# benjolin_1_0.net
KiCad netlist of a schematic drawn in EAGLE
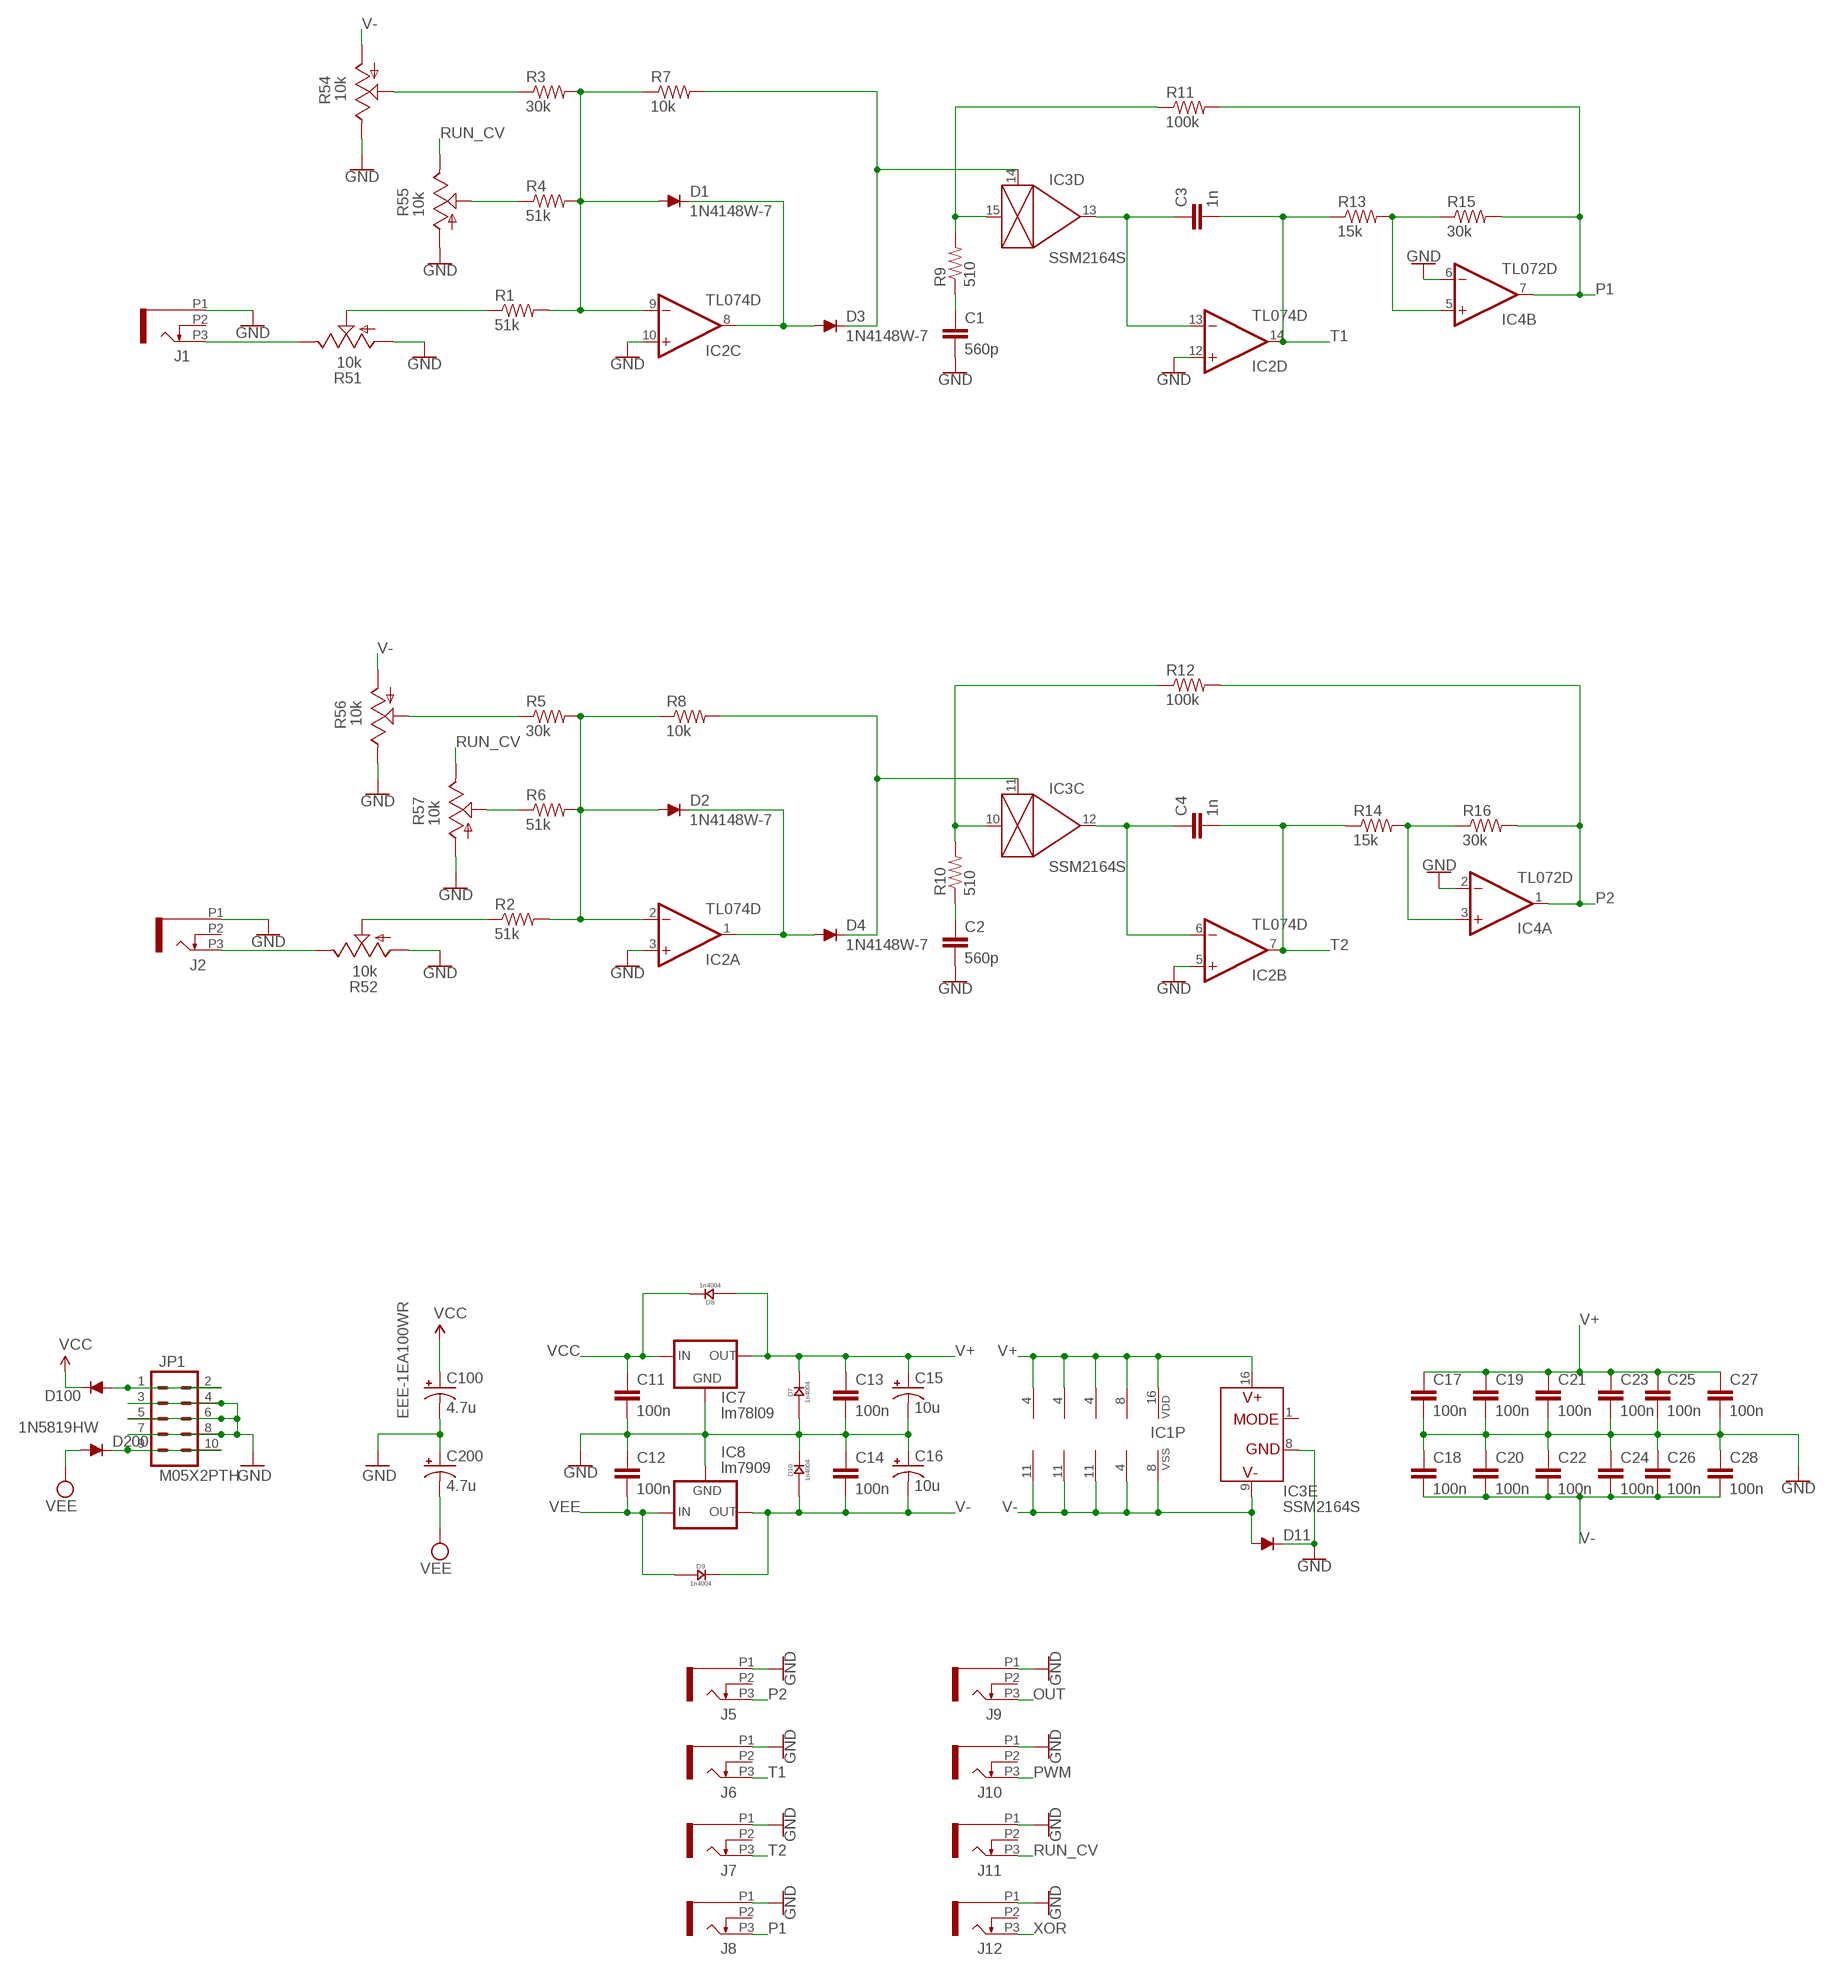
[diagram p0: schematic, sheet 1, part 1 of 2]
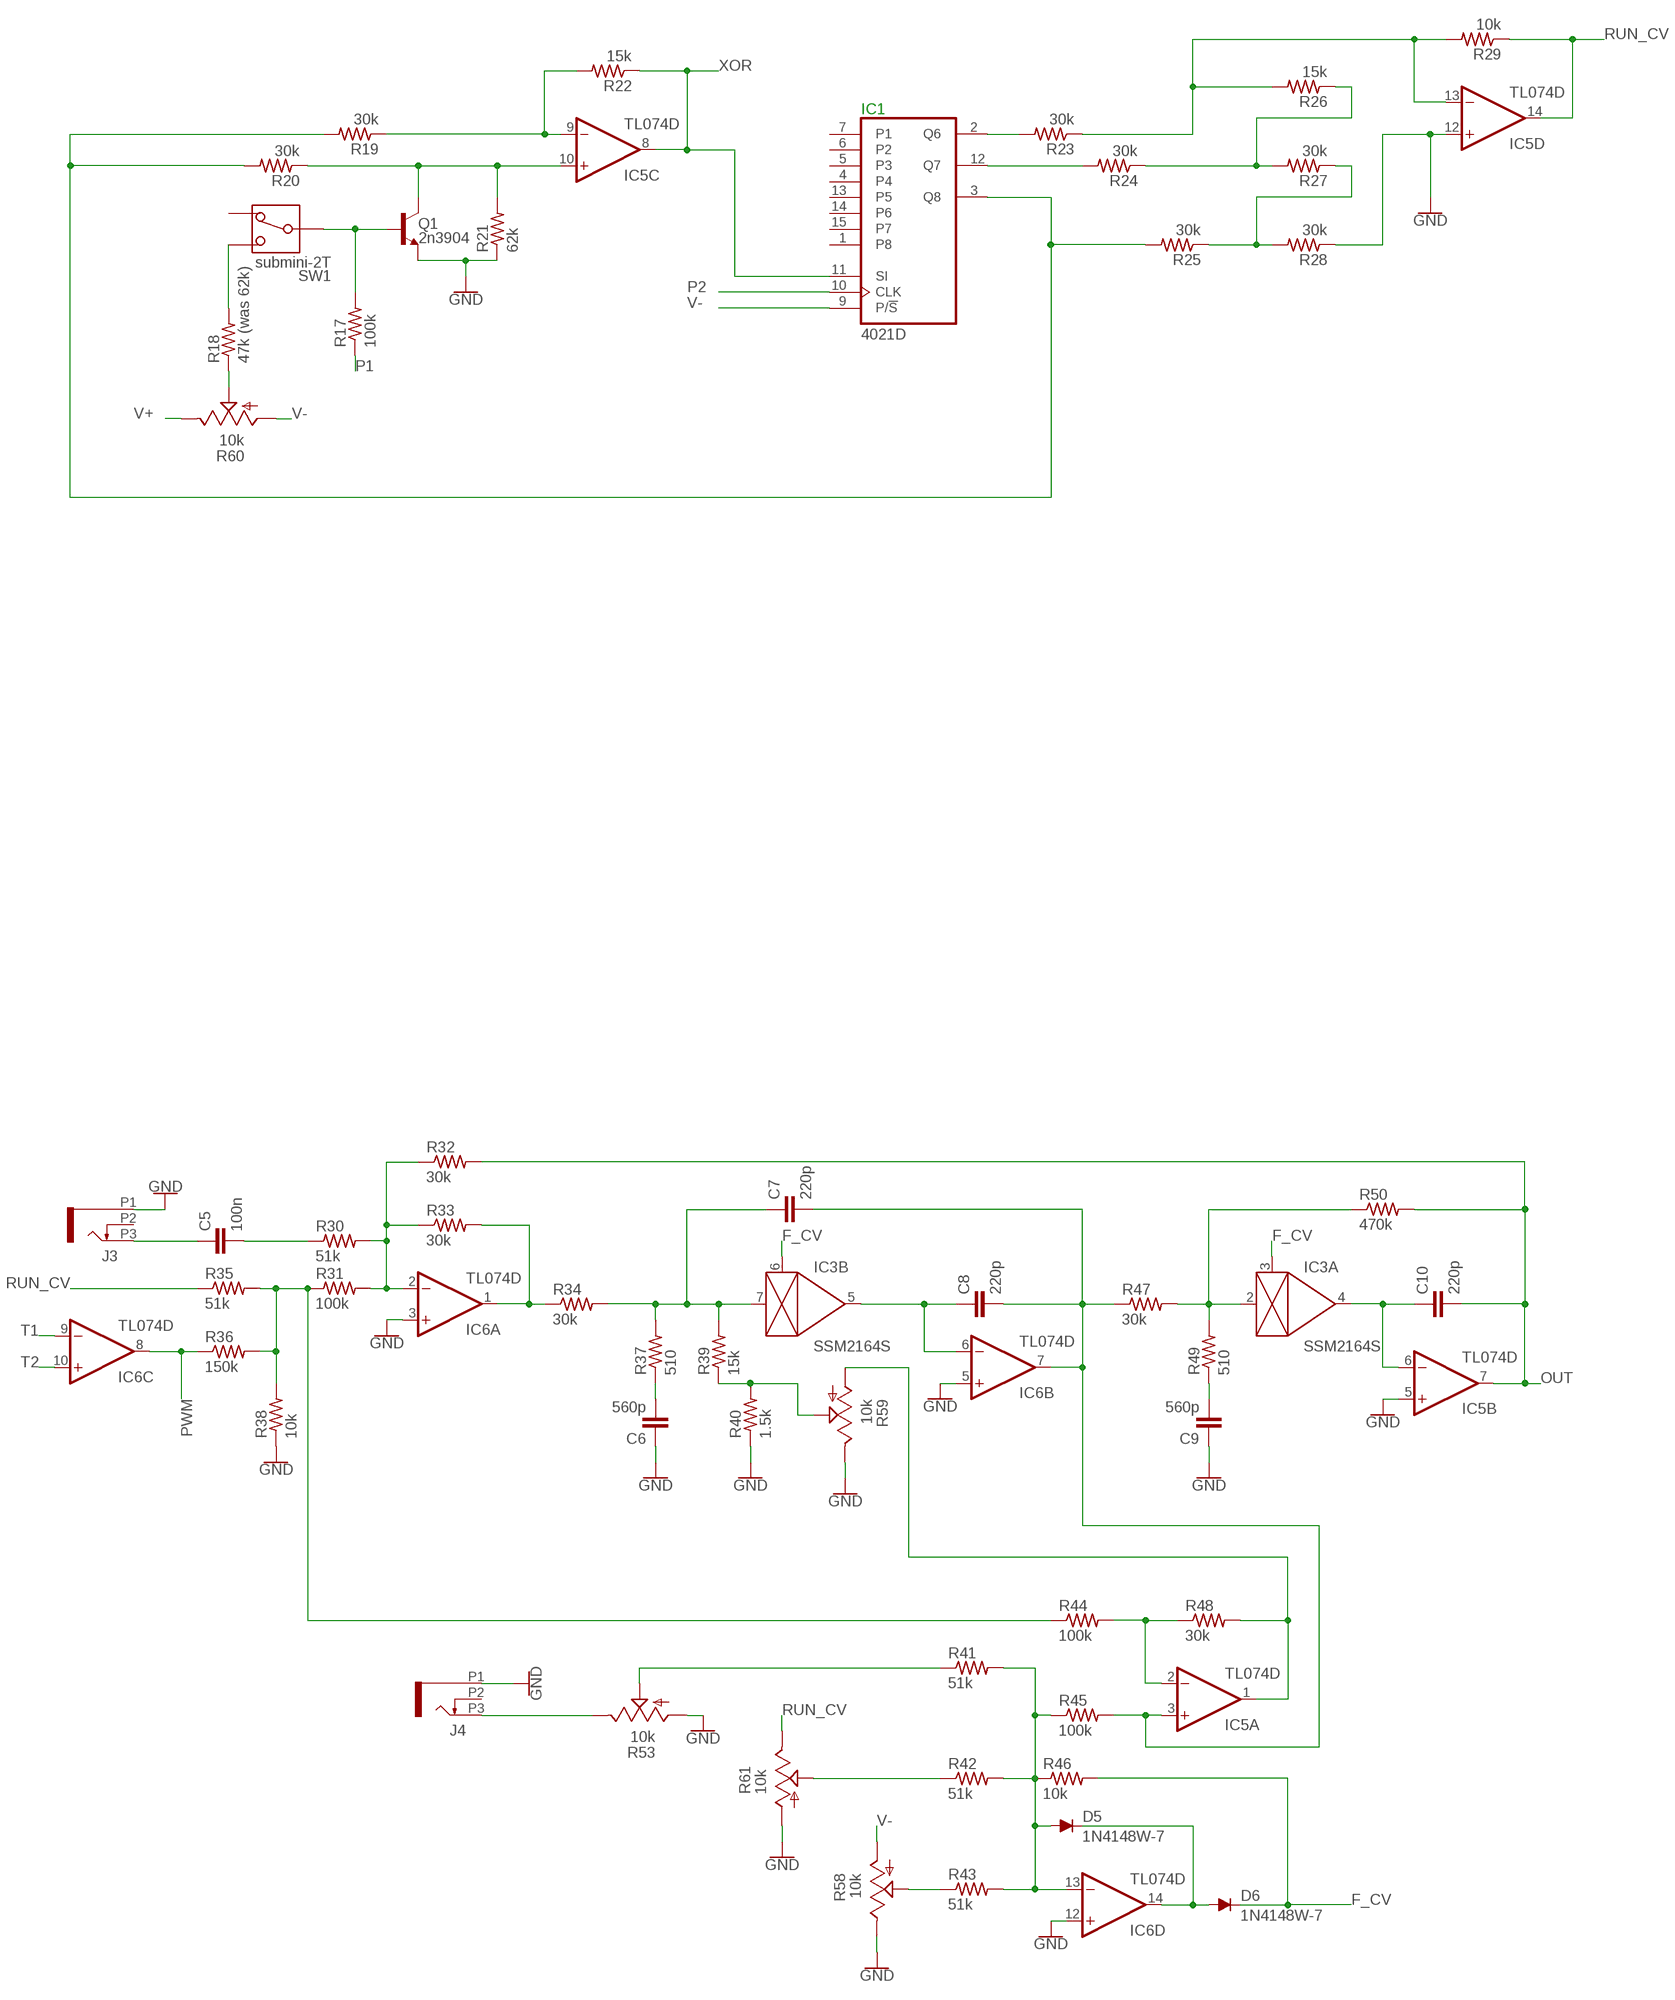
[diagram p1: schematic, sheet 1, part 2 of 2]

(export (version "E")
  (design (tool "Eeschema 10.0.6"))
  (components
    (comp (ref "C1")
      (value "560p")
      (footprint "eagle-import:C0603")
      (libsource (lib "eagle-import") (part "C-EUC0603"))
    )
    (comp (ref "C2")
      (value "560p")
      (footprint "eagle-import:C0603")
      (libsource (lib "eagle-import") (part "C-EUC0603"))
    )
    (comp (ref "C3")
      (value "1n")
      (footprint "eagle-import:C0603")
      (libsource (lib "eagle-import") (part "C-EUC0603"))
    )
    (comp (ref "C4")
      (value "1n")
      (footprint "eagle-import:C0603")
      (libsource (lib "eagle-import") (part "C-EUC0603"))
    )
    (comp (ref "C5")
      (value "100n")
      (footprint "eagle-import:C0603")
      (libsource (lib "eagle-import") (part "C-EUC0603"))
    )
    (comp (ref "C6")
      (value "560p")
      (footprint "eagle-import:C0603")
      (libsource (lib "eagle-import") (part "C-EUC0603"))
    )
    (comp (ref "C7")
      (value "220p")
      (footprint "eagle-import:C0603")
      (libsource (lib "eagle-import") (part "C-EUC0603"))
    )
    (comp (ref "C8")
      (value "220p")
      (footprint "eagle-import:C0603")
      (libsource (lib "eagle-import") (part "C-EUC0603"))
    )
    (comp (ref "C9")
      (value "560p")
      (footprint "eagle-import:C0603")
      (libsource (lib "eagle-import") (part "C-EUC0603"))
    )
    (comp (ref "C10")
      (value "220p")
      (footprint "eagle-import:C0603")
      (libsource (lib "eagle-import") (part "C-EUC0603"))
    )
    (comp (ref "C11")
      (value "100n")
      (footprint "eagle-import:C0603")
      (libsource (lib "eagle-import") (part "C-EUC0603"))
    )
    (comp (ref "C12")
      (value "100n")
      (footprint "eagle-import:C0603")
      (libsource (lib "eagle-import") (part "C-EUC0603"))
    )
    (comp (ref "C13")
      (value "100n")
      (footprint "eagle-import:C0603")
      (libsource (lib "eagle-import") (part "C-EUC0603"))
    )
    (comp (ref "C14")
      (value "100n")
      (footprint "eagle-import:C0603")
      (libsource (lib "eagle-import") (part "C-EUC0603"))
    )
    (comp (ref "C15")
      (value "10u")
      (footprint "eagle-import:PANASONIC_A")
      (libsource (lib "eagle-import") (part "CPOL-USA"))
    )
    (comp (ref "C16")
      (value "10u")
      (footprint "eagle-import:PANASONIC_A")
      (libsource (lib "eagle-import") (part "CPOL-USA"))
    )
    (comp (ref "C17")
      (value "100n")
      (footprint "eagle-import:C0603")
      (libsource (lib "eagle-import") (part "C-EUC0603"))
    )
    (comp (ref "C18")
      (value "100n")
      (footprint "eagle-import:C0603")
      (libsource (lib "eagle-import") (part "C-EUC0603"))
    )
    (comp (ref "C19")
      (value "100n")
      (footprint "eagle-import:C0603")
      (libsource (lib "eagle-import") (part "C-EUC0603"))
    )
    (comp (ref "C20")
      (value "100n")
      (footprint "eagle-import:C0603")
      (libsource (lib "eagle-import") (part "C-EUC0603"))
    )
    (comp (ref "C21")
      (value "100n")
      (footprint "eagle-import:C0603")
      (libsource (lib "eagle-import") (part "C-EUC0603"))
    )
    (comp (ref "C22")
      (value "100n")
      (footprint "eagle-import:C0603")
      (libsource (lib "eagle-import") (part "C-EUC0603"))
    )
    (comp (ref "C23")
      (value "100n")
      (footprint "eagle-import:C0603")
      (libsource (lib "eagle-import") (part "C-EUC0603"))
    )
    (comp (ref "C24")
      (value "100n")
      (footprint "eagle-import:C0603")
      (libsource (lib "eagle-import") (part "C-EUC0603"))
    )
    (comp (ref "C25")
      (value "100n")
      (footprint "eagle-import:C0603")
      (libsource (lib "eagle-import") (part "C-EUC0603"))
    )
    (comp (ref "C26")
      (value "100n")
      (footprint "eagle-import:C0603")
      (libsource (lib "eagle-import") (part "C-EUC0603"))
    )
    (comp (ref "C27")
      (value "100n")
      (footprint "eagle-import:C0603")
      (libsource (lib "eagle-import") (part "C-EUC0603"))
    )
    (comp (ref "C28")
      (value "100n")
      (footprint "eagle-import:C0603")
      (libsource (lib "eagle-import") (part "C-EUC0603"))
    )
    (comp (ref "C100")
      (value "4.7u")
      (footprint "eagle-import:PANASONIC_A")
      (libsource (lib "eagle-import") (part "CPOL-USA"))
    )
    (comp (ref "C200")
      (value "4.7u")
      (footprint "eagle-import:PANASONIC_A")
      (libsource (lib "eagle-import") (part "CPOL-USA"))
    )
    (comp (ref "D1")
      (value "1N4148W-7")
      (footprint "eagle-import:SOD123")
      (libsource (lib "eagle-import") (part "1N4148W-7"))
    )
    (comp (ref "D2")
      (value "1N4148W-7")
      (footprint "eagle-import:SOD123")
      (libsource (lib "eagle-import") (part "1N4148W-7"))
    )
    (comp (ref "D3")
      (value "1N4148W-7")
      (footprint "eagle-import:SOD123")
      (libsource (lib "eagle-import") (part "1N4148W-7"))
    )
    (comp (ref "D4")
      (value "1N4148W-7")
      (footprint "eagle-import:SOD123")
      (libsource (lib "eagle-import") (part "1N4148W-7"))
    )
    (comp (ref "D5")
      (value "1N4148W-7")
      (footprint "eagle-import:SOD123")
      (libsource (lib "eagle-import") (part "1N4148W-7"))
    )
    (comp (ref "D6")
      (value "1N4148W-7")
      (footprint "eagle-import:SOD123")
      (libsource (lib "eagle-import") (part "1N4148W-7"))
    )
    (comp (ref "D7")
      (value "1n4004")
      (footprint "eagle-import:DO-214AC")
      (libsource (lib "eagle-import") (part "D-SMA"))
    )
    (comp (ref "D8")
      (value "1n4004")
      (footprint "eagle-import:DO-214AC")
      (libsource (lib "eagle-import") (part "D-SMA"))
    )
    (comp (ref "D9")
      (value "1n4004")
      (footprint "eagle-import:DO-214AC")
      (libsource (lib "eagle-import") (part "D-SMA"))
    )
    (comp (ref "D10")
      (value "1n4004")
      (footprint "eagle-import:DO-214AC")
      (libsource (lib "eagle-import") (part "D-SMA"))
    )
    (comp (ref "D11")
      (value "1N5819HW")
      (footprint "eagle-import:SOD123")
      (libsource (lib "eagle-import") (part "DIODE-SOD123"))
    )
    (comp (ref "D100")
      (value "1N5819HW")
      (footprint "eagle-import:SOD123")
      (libsource (lib "eagle-import") (part "DIODE-SOD123"))
    )
    (comp (ref "D200")
      (value "1N5819HW")
      (footprint "eagle-import:SOD123")
      (libsource (lib "eagle-import") (part "DIODE-SOD123"))
    )
    (comp (ref "IC1")
      (value "4021D")
      (footprint "eagle-import:SO16")
      (libsource (lib "eagle-import") (part "4021D"))
    )
    (comp (ref "IC2")
      (value "TL074D")
      (footprint "eagle-import:SO14")
      (libsource (lib "eagle-import") (part "TL074D"))
    )
    (comp (ref "IC3")
      (value "SSM2164S")
      (footprint "eagle-import:SOIC16N")
      (libsource (lib "eagle-import") (part "SSM2164S"))
    )
    (comp (ref "IC4")
      (value "TL072D")
      (footprint "eagle-import:SO08")
      (libsource (lib "eagle-import") (part "TL072D"))
    )
    (comp (ref "IC5")
      (value "TL074D")
      (footprint "eagle-import:SO14")
      (libsource (lib "eagle-import") (part "TL074D"))
    )
    (comp (ref "IC6")
      (value "TL074D")
      (footprint "eagle-import:SO14")
      (libsource (lib "eagle-import") (part "TL074D"))
    )
    (comp (ref "IC7")
      (value "lm78l09")
      (footprint "eagle-import:78LXX")
      (libsource (lib "eagle-import") (part "78LXX"))
    )
    (comp (ref "IC8")
      (value "lm7909")
      (footprint "eagle-import:79LXX")
      (libsource (lib "eagle-import") (part "79LXX"))
    )
    (comp (ref "J1")
      (value "PJ301_THONKICONN6")
      (footprint "eagle-import:WQP_PJ_301M6")
      (libsource (lib "eagle-import") (part "PJ301_THONKICONN6"))
    )
    (comp (ref "J2")
      (value "PJ301_THONKICONN6")
      (footprint "eagle-import:WQP_PJ_301M6")
      (libsource (lib "eagle-import") (part "PJ301_THONKICONN6"))
    )
    (comp (ref "J3")
      (value "PJ301_THONKICONN6")
      (footprint "eagle-import:WQP_PJ_301M6")
      (libsource (lib "eagle-import") (part "PJ301_THONKICONN6"))
    )
    (comp (ref "J4")
      (value "PJ301_THONKICONN6")
      (footprint "eagle-import:WQP_PJ_301M6")
      (libsource (lib "eagle-import") (part "PJ301_THONKICONN6"))
    )
    (comp (ref "J5")
      (value "PJ301_THONKICONN6")
      (footprint "eagle-import:WQP_PJ_301M6")
      (libsource (lib "eagle-import") (part "PJ301_THONKICONN6"))
    )
    (comp (ref "J6")
      (value "PJ301_THONKICONN6")
      (footprint "eagle-import:WQP_PJ_301M6")
      (libsource (lib "eagle-import") (part "PJ301_THONKICONN6"))
    )
    (comp (ref "J7")
      (value "PJ301_THONKICONN6")
      (footprint "eagle-import:WQP_PJ_301M6")
      (libsource (lib "eagle-import") (part "PJ301_THONKICONN6"))
    )
    (comp (ref "J8")
      (value "PJ301_THONKICONN6")
      (footprint "eagle-import:WQP_PJ_301M6")
      (libsource (lib "eagle-import") (part "PJ301_THONKICONN6"))
    )
    (comp (ref "J9")
      (value "PJ301_THONKICONN6")
      (footprint "eagle-import:WQP_PJ_301M6")
      (libsource (lib "eagle-import") (part "PJ301_THONKICONN6"))
    )
    (comp (ref "J10")
      (value "PJ301_THONKICONN6")
      (footprint "eagle-import:WQP_PJ_301M6")
      (libsource (lib "eagle-import") (part "PJ301_THONKICONN6"))
    )
    (comp (ref "J11")
      (value "PJ301_THONKICONN6")
      (footprint "eagle-import:WQP_PJ_301M6")
      (libsource (lib "eagle-import") (part "PJ301_THONKICONN6"))
    )
    (comp (ref "J12")
      (value "PJ301_THONKICONN6")
      (footprint "eagle-import:WQP_PJ_301M6")
      (libsource (lib "eagle-import") (part "PJ301_THONKICONN6"))
    )
    (comp (ref "JP1")
      (value "M05X2PTH")
      (footprint "eagle-import:AVR_ICSP")
      (libsource (lib "eagle-import") (part "M05X2PTH"))
    )
    (comp (ref "Q1")
      (value "2n3904")
      (footprint "eagle-import:SOT23-3")
      (libsource (lib "eagle-import") (part "TRANS_NPN-MMBT2222AL"))
    )
    (comp (ref "R1")
      (value "51k")
      (footprint "eagle-import:R0603")
      (libsource (lib "eagle-import") (part "R-US_R0603"))
    )
    (comp (ref "R2")
      (value "51k")
      (footprint "eagle-import:R0603")
      (libsource (lib "eagle-import") (part "R-US_R0603"))
    )
    (comp (ref "R3")
      (value "30k")
      (footprint "eagle-import:R0603")
      (libsource (lib "eagle-import") (part "R-US_R0603"))
    )
    (comp (ref "R4")
      (value "51k")
      (footprint "eagle-import:R0603")
      (libsource (lib "eagle-import") (part "R-US_R0603"))
    )
    (comp (ref "R5")
      (value "30k")
      (footprint "eagle-import:R0603")
      (libsource (lib "eagle-import") (part "R-US_R0603"))
    )
    (comp (ref "R6")
      (value "51k")
      (footprint "eagle-import:R0603")
      (libsource (lib "eagle-import") (part "R-US_R0603"))
    )
    (comp (ref "R7")
      (value "10k")
      (footprint "eagle-import:R0603")
      (libsource (lib "eagle-import") (part "R-US_R0603"))
    )
    (comp (ref "R8")
      (value "10k")
      (footprint "eagle-import:R0603")
      (libsource (lib "eagle-import") (part "R-US_R0603"))
    )
    (comp (ref "R9")
      (value "510")
      (footprint "eagle-import:R0603")
      (libsource (lib "eagle-import") (part "R-US_R0603"))
    )
    (comp (ref "R10")
      (value "510")
      (footprint "eagle-import:R0603")
      (libsource (lib "eagle-import") (part "R-US_R0603"))
    )
    (comp (ref "R11")
      (value "100k")
      (footprint "eagle-import:R0603")
      (libsource (lib "eagle-import") (part "R-US_R0603"))
    )
    (comp (ref "R12")
      (value "100k")
      (footprint "eagle-import:R0603")
      (libsource (lib "eagle-import") (part "R-US_R0603"))
    )
    (comp (ref "R13")
      (value "15k")
      (footprint "eagle-import:R0603")
      (libsource (lib "eagle-import") (part "R-US_R0603"))
    )
    (comp (ref "R14")
      (value "15k")
      (footprint "eagle-import:R0603")
      (libsource (lib "eagle-import") (part "R-US_R0603"))
    )
    (comp (ref "R15")
      (value "30k")
      (footprint "eagle-import:R0603")
      (libsource (lib "eagle-import") (part "R-US_R0603"))
    )
    (comp (ref "R16")
      (value "30k")
      (footprint "eagle-import:R0603")
      (libsource (lib "eagle-import") (part "R-US_R0603"))
    )
    (comp (ref "R17")
      (value "100k")
      (footprint "eagle-import:R0603")
      (libsource (lib "eagle-import") (part "R-US_R0603"))
    )
    (comp (ref "R18")
      (value "47k (was 62k)")
      (footprint "eagle-import:R0603")
      (libsource (lib "eagle-import") (part "R-US_R0603"))
    )
    (comp (ref "R19")
      (value "30k")
      (footprint "eagle-import:R0603")
      (libsource (lib "eagle-import") (part "R-US_R0603"))
    )
    (comp (ref "R20")
      (value "30k")
      (footprint "eagle-import:R0603")
      (libsource (lib "eagle-import") (part "R-US_R0603"))
    )
    (comp (ref "R21")
      (value "62k")
      (footprint "eagle-import:R0603")
      (libsource (lib "eagle-import") (part "R-US_R0603"))
    )
    (comp (ref "R22")
      (value "15k")
      (footprint "eagle-import:R0603")
      (libsource (lib "eagle-import") (part "R-US_R0603"))
    )
    (comp (ref "R23")
      (value "30k")
      (footprint "eagle-import:R0603")
      (libsource (lib "eagle-import") (part "R-US_R0603"))
    )
    (comp (ref "R24")
      (value "30k")
      (footprint "eagle-import:R0603")
      (libsource (lib "eagle-import") (part "R-US_R0603"))
    )
    (comp (ref "R25")
      (value "30k")
      (footprint "eagle-import:R0603")
      (libsource (lib "eagle-import") (part "R-US_R0603"))
    )
    (comp (ref "R26")
      (value "15k")
      (footprint "eagle-import:R0603")
      (libsource (lib "eagle-import") (part "R-US_R0603"))
    )
    (comp (ref "R27")
      (value "30k")
      (footprint "eagle-import:R0603")
      (libsource (lib "eagle-import") (part "R-US_R0603"))
    )
    (comp (ref "R28")
      (value "30k")
      (footprint "eagle-import:R0603")
      (libsource (lib "eagle-import") (part "R-US_R0603"))
    )
    (comp (ref "R29")
      (value "10k")
      (footprint "eagle-import:R0603")
      (libsource (lib "eagle-import") (part "R-US_R0603"))
    )
    (comp (ref "R30")
      (value "51k")
      (footprint "eagle-import:R0603")
      (libsource (lib "eagle-import") (part "R-US_R0603"))
    )
    (comp (ref "R31")
      (value "100k")
      (footprint "eagle-import:R0603")
      (libsource (lib "eagle-import") (part "R-US_R0603"))
    )
    (comp (ref "R32")
      (value "30k")
      (footprint "eagle-import:R0603")
      (libsource (lib "eagle-import") (part "R-US_R0603"))
    )
    (comp (ref "R33")
      (value "30k")
      (footprint "eagle-import:R0603")
      (libsource (lib "eagle-import") (part "R-US_R0603"))
    )
    (comp (ref "R34")
      (value "30k")
      (footprint "eagle-import:R0603")
      (libsource (lib "eagle-import") (part "R-US_R0603"))
    )
    (comp (ref "R35")
      (value "51k")
      (footprint "eagle-import:R0603")
      (libsource (lib "eagle-import") (part "R-US_R0603"))
    )
    (comp (ref "R36")
      (value "150k")
      (footprint "eagle-import:R0603")
      (libsource (lib "eagle-import") (part "R-US_R0603"))
    )
    (comp (ref "R37")
      (value "510")
      (footprint "eagle-import:R0603")
      (libsource (lib "eagle-import") (part "R-US_R0603"))
    )
    (comp (ref "R38")
      (value "10k")
      (footprint "eagle-import:R0603")
      (libsource (lib "eagle-import") (part "R-US_R0603"))
    )
    (comp (ref "R39")
      (value "15k")
      (footprint "eagle-import:R0603")
      (libsource (lib "eagle-import") (part "R-US_R0603"))
    )
    (comp (ref "R40")
      (value "1.5k")
      (footprint "eagle-import:R0603")
      (libsource (lib "eagle-import") (part "R-US_R0603"))
    )
    (comp (ref "R41")
      (value "51k")
      (footprint "eagle-import:R0603")
      (libsource (lib "eagle-import") (part "R-US_R0603"))
    )
    (comp (ref "R42")
      (value "51k")
      (footprint "eagle-import:R0603")
      (libsource (lib "eagle-import") (part "R-US_R0603"))
    )
    (comp (ref "R43")
      (value "51k")
      (footprint "eagle-import:R0603")
      (libsource (lib "eagle-import") (part "R-US_R0603"))
    )
    (comp (ref "R44")
      (value "100k")
      (footprint "eagle-import:R0603")
      (libsource (lib "eagle-import") (part "R-US_R0603"))
    )
    (comp (ref "R45")
      (value "100k")
      (footprint "eagle-import:R0603")
      (libsource (lib "eagle-import") (part "R-US_R0603"))
    )
    (comp (ref "R46")
      (value "10k")
      (footprint "eagle-import:R0603")
      (libsource (lib "eagle-import") (part "R-US_R0603"))
    )
    (comp (ref "R47")
      (value "30k")
      (footprint "eagle-import:R0603")
      (libsource (lib "eagle-import") (part "R-US_R0603"))
    )
    (comp (ref "R48")
      (value "30k")
      (footprint "eagle-import:R0603")
      (libsource (lib "eagle-import") (part "R-US_R0603"))
    )
    (comp (ref "R49")
      (value "510")
      (footprint "eagle-import:R0603")
      (libsource (lib "eagle-import") (part "R-US_R0603"))
    )
    (comp (ref "R50")
      (value "470k")
      (footprint "eagle-import:R0603")
      (libsource (lib "eagle-import") (part "R-US_R0603"))
    )
    (comp (ref "R51")
      (value "10k")
      (footprint "eagle-import:ALPS_POT_NARROW")
      (libsource (lib "eagle-import") (part "POT_USVERTICAL_NARROW"))
    )
    (comp (ref "R52")
      (value "10k")
      (footprint "eagle-import:ALPS_POT_NARROW")
      (libsource (lib "eagle-import") (part "POT_USVERTICAL_NARROW"))
    )
    (comp (ref "R53")
      (value "10k")
      (footprint "eagle-import:ALPS_POT_NARROW")
      (libsource (lib "eagle-import") (part "POT_USVERTICAL_NARROW"))
    )
    (comp (ref "R54")
      (value "10k")
      (footprint "eagle-import:ALPS_POT_VERTICAL_PS")
      (libsource (lib "eagle-import") (part "POT_USVERTICAL_PS"))
    )
    (comp (ref "R55")
      (value "10k")
      (footprint "eagle-import:ALPS_POT_VERTICAL_PS")
      (libsource (lib "eagle-import") (part "POT_USVERTICAL_PS"))
    )
    (comp (ref "R56")
      (value "10k")
      (footprint "eagle-import:ALPS_POT_VERTICAL_PS")
      (libsource (lib "eagle-import") (part "POT_USVERTICAL_PS"))
    )
    (comp (ref "R57")
      (value "10k")
      (footprint "eagle-import:ALPS_POT_VERTICAL_PS")
      (libsource (lib "eagle-import") (part "POT_USVERTICAL_PS"))
    )
    (comp (ref "R58")
      (value "10k")
      (footprint "eagle-import:ALPS_POT_VERTICAL_PS")
      (libsource (lib "eagle-import") (part "POT_USVERTICAL_PS"))
    )
    (comp (ref "R59")
      (value "10k")
      (footprint "eagle-import:ALPS_POT_VERTICAL_PS")
      (libsource (lib "eagle-import") (part "POT_USVERTICAL_PS"))
    )
    (comp (ref "R60")
      (value "10k")
      (footprint "eagle-import:ALPS_POT_VERTICAL_PS")
      (libsource (lib "eagle-import") (part "POT_USVERTICAL_PS"))
    )
    (comp (ref "R61")
      (value "10k")
      (footprint "eagle-import:ALPS_POT_VERTICAL_PS")
      (libsource (lib "eagle-import") (part "POT_USVERTICAL_PS"))
    )
    (comp (ref "SW1")
      (value "submini-2T")
      (footprint "eagle-import:SPDT-SUB")
      (libsource (lib "eagle-import") (part "SPDTT"))
    )
  )
  (nets
    (net (code "1") (name "F_CV") (class "Default")
      (node (ref "D6") (pin "C") (pinfunction "C_C") (pintype "passive"))
      (node (ref "IC3") (pin "3") (pinfunction "CTRL_3") (pintype "input"))
      (node (ref "IC3") (pin "6") (pinfunction "CTRL_6") (pintype "input"))
      (node (ref "R46") (pin "2") (pinfunction "2_2") (pintype "passive"))
    )
    (net (code "2") (name "GND") (class "Default")
      (node (ref "C1") (pin "2") (pinfunction "2_2") (pintype "passive"))
      (node (ref "C100") (pin "-") (pinfunction "-_-") (pintype "passive"))
      (node (ref "C11") (pin "2") (pinfunction "2_2") (pintype "passive"))
      (node (ref "C12") (pin "1") (pinfunction "1_1") (pintype "passive"))
      (node (ref "C13") (pin "2") (pinfunction "2_2") (pintype "passive"))
      (node (ref "C14") (pin "1") (pinfunction "1_1") (pintype "passive"))
      (node (ref "C15") (pin "-") (pinfunction "-_-") (pintype "passive"))
      (node (ref "C16") (pin "+") (pinfunction "+_+") (pintype "passive"))
      (node (ref "C17") (pin "2") (pinfunction "2_2") (pintype "passive"))
      (node (ref "C18") (pin "1") (pinfunction "1_1") (pintype "passive"))
      (node (ref "C19") (pin "2") (pinfunction "2_2") (pintype "passive"))
      (node (ref "C2") (pin "2") (pinfunction "2_2") (pintype "passive"))
      (node (ref "C20") (pin "1") (pinfunction "1_1") (pintype "passive"))
      (node (ref "C200") (pin "+") (pinfunction "+_+") (pintype "passive"))
      (node (ref "C21") (pin "2") (pinfunction "2_2") (pintype "passive"))
      (node (ref "C22") (pin "1") (pinfunction "1_1") (pintype "passive"))
      (node (ref "C23") (pin "2") (pinfunction "2_2") (pintype "passive"))
      (node (ref "C24") (pin "1") (pinfunction "1_1") (pintype "passive"))
      (node (ref "C25") (pin "2") (pinfunction "2_2") (pintype "passive"))
      (node (ref "C26") (pin "1") (pinfunction "1_1") (pintype "passive"))
      (node (ref "C27") (pin "2") (pinfunction "2_2") (pintype "passive"))
      (node (ref "C28") (pin "1") (pinfunction "1_1") (pintype "passive"))
      (node (ref "C6") (pin "1") (pinfunction "1_1") (pintype "passive"))
      (node (ref "C9") (pin "1") (pinfunction "1_1") (pintype "passive"))
      (node (ref "D10") (pin "2") (pinfunction "-_2") (pintype "passive"))
      (node (ref "D11") (pin "C") (pinfunction "C_C") (pintype "passive"))
      (node (ref "D7") (pin "1") (pinfunction "+_1") (pintype "passive"))
      (node (ref "IC2") (pin "10") (pinfunction "+IN_10") (pintype "input"))
      (node (ref "IC2") (pin "12") (pinfunction "+IN_12") (pintype "input"))
      (node (ref "IC2") (pin "3") (pinfunction "+IN_3") (pintype "input"))
      (node (ref "IC2") (pin "5") (pinfunction "+IN_5") (pintype "input"))
      (node (ref "IC3") (pin "8") (pinfunction "GND_8") (pintype "power_in"))
      (node (ref "IC4") (pin "2") (pinfunction "-IN_2") (pintype "input"))
      (node (ref "IC4") (pin "6") (pinfunction "-IN_6") (pintype "input"))
      (node (ref "IC5") (pin "12") (pinfunction "+IN_12") (pintype "input"))
      (node (ref "IC5") (pin "5") (pinfunction "+IN_5") (pintype "input"))
      (node (ref "IC6") (pin "12") (pinfunction "+IN_12") (pintype "input"))
      (node (ref "IC6") (pin "3") (pinfunction "+IN_3") (pintype "input"))
      (node (ref "IC6") (pin "5") (pinfunction "+IN_5") (pintype "input"))
      (node (ref "IC7") (pin "GND") (pinfunction "GND_GND") (pintype "input"))
      (node (ref "IC8") (pin "GND") (pinfunction "GND_GND") (pintype "input"))
      (node (ref "J1") (pin "P1") (pinfunction "1_P1") (pintype "passive"))
      (node (ref "J10") (pin "P1") (pinfunction "1_P1") (pintype "passive"))
      (node (ref "J11") (pin "P1") (pinfunction "1_P1") (pintype "passive"))
      (node (ref "J12") (pin "P1") (pinfunction "1_P1") (pintype "passive"))
      (node (ref "J2") (pin "P1") (pinfunction "1_P1") (pintype "passive"))
      (node (ref "J3") (pin "P1") (pinfunction "1_P1") (pintype "passive"))
      (node (ref "J4") (pin "P1") (pinfunction "1_P1") (pintype "passive"))
      (node (ref "J5") (pin "P1") (pinfunction "1_P1") (pintype "passive"))
      (node (ref "J6") (pin "P1") (pinfunction "1_P1") (pintype "passive"))
      (node (ref "J7") (pin "P1") (pinfunction "1_P1") (pintype "passive"))
      (node (ref "J8") (pin "P1") (pinfunction "1_P1") (pintype "passive"))
      (node (ref "J9") (pin "P1") (pinfunction "1_P1") (pintype "passive"))
      (node (ref "JP1") (pin "3") (pinfunction "3_3") (pintype "passive"))
      (node (ref "JP1") (pin "4") (pinfunction "4_4") (pintype "passive"))
      (node (ref "JP1") (pin "5") (pinfunction "5_5") (pintype "passive"))
      (node (ref "JP1") (pin "6") (pinfunction "6_6") (pintype "passive"))
      (node (ref "JP1") (pin "7") (pinfunction "7_7") (pintype "passive"))
      (node (ref "JP1") (pin "8") (pinfunction "8_8") (pintype "passive"))
      (node (ref "Q1") (pin "2") (pinfunction "E_2") (pintype "passive"))
      (node (ref "R21") (pin "1") (pinfunction "1_1") (pintype "passive"))
      (node (ref "R28") (pin "1") (pinfunction "1_1") (pintype "passive"))
      (node (ref "R38") (pin "1") (pinfunction "1_1") (pintype "passive"))
      (node (ref "R40") (pin "1") (pinfunction "1_1") (pintype "passive"))
      (node (ref "R51") (pin "P$3") (pinfunction "A_P$3") (pintype "passive"))
      (node (ref "R52") (pin "P$3") (pinfunction "A_P$3") (pintype "passive"))
      (node (ref "R53") (pin "P$3") (pinfunction "A_P$3") (pintype "passive"))
      (node (ref "R54") (pin "P$1") (pinfunction "E_P$1") (pintype "passive"))
      (node (ref "R55") (pin "P$3") (pinfunction "A_P$3") (pintype "passive"))
      (node (ref "R56") (pin "P$1") (pinfunction "E_P$1") (pintype "passive"))
      (node (ref "R57") (pin "P$3") (pinfunction "A_P$3") (pintype "passive"))
      (node (ref "R58") (pin "P$1") (pinfunction "E_P$1") (pintype "passive"))
      (node (ref "R59") (pin "P$1") (pinfunction "E_P$1") (pintype "passive"))
      (node (ref "R61") (pin "P$3") (pinfunction "A_P$3") (pintype "passive"))
    )
    (net (code "3") (name "Net-(C1-Pad1)") (class "Default")
      (node (ref "C1") (pin "1") (pinfunction "1_1") (pintype "passive"))
      (node (ref "R9") (pin "1") (pinfunction "1_1") (pintype "passive"))
    )
    (net (code "4") (name "Net-(C2-Pad1)") (class "Default")
      (node (ref "C2") (pin "1") (pinfunction "1_1") (pintype "passive"))
      (node (ref "R10") (pin "1") (pinfunction "1_1") (pintype "passive"))
    )
    (net (code "5") (name "Net-(C5-Pad2)") (class "Default")
      (node (ref "C5") (pin "2") (pinfunction "2_2") (pintype "passive"))
      (node (ref "R30") (pin "1") (pinfunction "1_1") (pintype "passive"))
    )
    (net (code "6") (name "Net-(C6-Pad2)") (class "Default")
      (node (ref "C6") (pin "2") (pinfunction "2_2") (pintype "passive"))
      (node (ref "R37") (pin "1") (pinfunction "1_1") (pintype "passive"))
    )
    (net (code "7") (name "Net-(C9-Pad2)") (class "Default")
      (node (ref "C9") (pin "2") (pinfunction "2_2") (pintype "passive"))
      (node (ref "R49") (pin "1") (pinfunction "1_1") (pintype "passive"))
    )
    (net (code "8") (name "Net-(D100-PadA)") (class "Default")
      (node (ref "D100") (pin "A") (pinfunction "A_A") (pintype "passive"))
      (node (ref "JP1") (pin "1") (pinfunction "1_1") (pintype "passive"))
      (node (ref "JP1") (pin "2") (pinfunction "2_2") (pintype "passive"))
    )
    (net (code "9") (name "Net-(D200-PadC)") (class "Default")
      (node (ref "D200") (pin "C") (pinfunction "C_C") (pintype "passive"))
      (node (ref "JP1") (pin "10") (pinfunction "10_10") (pintype "passive"))
      (node (ref "JP1") (pin "9") (pinfunction "9_9") (pintype "passive"))
    )
    (net (code "10") (name "Net-(IC1A-Q6)") (class "Default")
      (node (ref "IC1") (pin "2") (pinfunction "Q6_2") (pintype "output"))
      (node (ref "R23") (pin "2") (pinfunction "2_2") (pintype "passive"))
    )
    (net (code "11") (name "Net-(IC1A-Q7)") (class "Default")
      (node (ref "IC1") (pin "12") (pinfunction "Q7_12") (pintype "output"))
      (node (ref "R24") (pin "2") (pinfunction "2_2") (pintype "passive"))
    )
    (net (code "12") (name "Net-(IC1A-Q8)") (class "Default")
      (node (ref "IC1") (pin "3") (pinfunction "Q8_3") (pintype "output"))
      (node (ref "R19") (pin "2") (pinfunction "2_2") (pintype "passive"))
      (node (ref "R20") (pin "2") (pinfunction "2_2") (pintype "passive"))
      (node (ref "R25") (pin "2") (pinfunction "2_2") (pintype "passive"))
    )
    (net (code "13") (name "Net-(IC2A--IN)") (class "Default")
      (node (ref "D2") (pin "A") (pinfunction "A_A") (pintype "passive"))
      (node (ref "IC2") (pin "2") (pinfunction "-IN_2") (pintype "input"))
      (node (ref "R2") (pin "2") (pinfunction "2_2") (pintype "passive"))
      (node (ref "R5") (pin "2") (pinfunction "2_2") (pintype "passive"))
      (node (ref "R6") (pin "2") (pinfunction "2_2") (pintype "passive"))
      (node (ref "R8") (pin "1") (pinfunction "1_1") (pintype "passive"))
    )
    (net (code "14") (name "Net-(IC2A-OUT)") (class "Default")
      (node (ref "D2") (pin "C") (pinfunction "C_C") (pintype "passive"))
      (node (ref "D4") (pin "A") (pinfunction "A_A") (pintype "passive"))
      (node (ref "IC2") (pin "1") (pinfunction "OUT_1") (pintype "output"))
    )
    (net (code "15") (name "Net-(IC2B--IN)") (class "Default")
      (node (ref "C4") (pin "1") (pinfunction "1_1") (pintype "passive"))
      (node (ref "IC2") (pin "6") (pinfunction "-IN_6") (pintype "input"))
      (node (ref "IC3") (pin "12") (pinfunction "OUT_12") (pintype "output"))
    )
    (net (code "16") (name "Net-(IC2C--IN)") (class "Default")
      (node (ref "D1") (pin "A") (pinfunction "A_A") (pintype "passive"))
      (node (ref "IC2") (pin "9") (pinfunction "-IN_9") (pintype "input"))
      (node (ref "R1") (pin "2") (pinfunction "2_2") (pintype "passive"))
      (node (ref "R3") (pin "2") (pinfunction "2_2") (pintype "passive"))
      (node (ref "R4") (pin "2") (pinfunction "2_2") (pintype "passive"))
      (node (ref "R7") (pin "1") (pinfunction "1_1") (pintype "passive"))
    )
    (net (code "17") (name "Net-(IC2C-OUT)") (class "Default")
      (node (ref "D1") (pin "C") (pinfunction "C_C") (pintype "passive"))
      (node (ref "D3") (pin "A") (pinfunction "A_A") (pintype "passive"))
      (node (ref "IC2") (pin "8") (pinfunction "OUT_8") (pintype "output"))
    )
    (net (code "18") (name "Net-(IC2D--IN)") (class "Default")
      (node (ref "C3") (pin "1") (pinfunction "1_1") (pintype "passive"))
      (node (ref "IC2") (pin "13") (pinfunction "-IN_13") (pintype "input"))
      (node (ref "IC3") (pin "13") (pinfunction "OUT_13") (pintype "output"))
    )
    (net (code "19") (name "Net-(IC3A-IN)") (class "Default")
      (node (ref "IC3") (pin "2") (pinfunction "IN_2") (pintype "input"))
      (node (ref "R47") (pin "2") (pinfunction "2_2") (pintype "passive"))
      (node (ref "R49") (pin "2") (pinfunction "2_2") (pintype "passive"))
      (node (ref "R50") (pin "1") (pinfunction "1_1") (pintype "passive"))
    )
    (net (code "20") (name "Net-(IC3A-OUT)") (class "Default")
      (node (ref "C10") (pin "1") (pinfunction "1_1") (pintype "passive"))
      (node (ref "IC3") (pin "4") (pinfunction "OUT_4") (pintype "output"))
      (node (ref "IC5") (pin "6") (pinfunction "-IN_6") (pintype "input"))
    )
    (net (code "21") (name "Net-(IC3B-IN)") (class "Default")
      (node (ref "C7") (pin "1") (pinfunction "1_1") (pintype "passive"))
      (node (ref "IC3") (pin "7") (pinfunction "IN_7") (pintype "input"))
      (node (ref "R34") (pin "2") (pinfunction "2_2") (pintype "passive"))
      (node (ref "R37") (pin "2") (pinfunction "2_2") (pintype "passive"))
      (node (ref "R39") (pin "2") (pinfunction "2_2") (pintype "passive"))
    )
    (net (code "22") (name "Net-(IC3B-OUT)") (class "Default")
      (node (ref "C8") (pin "1") (pinfunction "1_1") (pintype "passive"))
      (node (ref "IC3") (pin "5") (pinfunction "OUT_5") (pintype "output"))
      (node (ref "IC6") (pin "6") (pinfunction "-IN_6") (pintype "input"))
    )
    (net (code "23") (name "Net-(IC3C-CTRL)") (class "Default")
      (node (ref "D4") (pin "C") (pinfunction "C_C") (pintype "passive"))
      (node (ref "IC3") (pin "11") (pinfunction "CTRL_11") (pintype "input"))
      (node (ref "R8") (pin "2") (pinfunction "2_2") (pintype "passive"))
    )
    (net (code "24") (name "Net-(IC3C-IN)") (class "Default")
      (node (ref "IC3") (pin "10") (pinfunction "IN_10") (pintype "input"))
      (node (ref "R10") (pin "2") (pinfunction "2_2") (pintype "passive"))
      (node (ref "R12") (pin "1") (pinfunction "1_1") (pintype "passive"))
    )
    (net (code "25") (name "Net-(IC3D-CTRL)") (class "Default")
      (node (ref "D3") (pin "C") (pinfunction "C_C") (pintype "passive"))
      (node (ref "IC3") (pin "14") (pinfunction "CTRL_14") (pintype "input"))
      (node (ref "R7") (pin "2") (pinfunction "2_2") (pintype "passive"))
    )
    (net (code "26") (name "Net-(IC3D-IN)") (class "Default")
      (node (ref "IC3") (pin "15") (pinfunction "IN_15") (pintype "input"))
      (node (ref "R11") (pin "1") (pinfunction "1_1") (pintype "passive"))
      (node (ref "R9") (pin "2") (pinfunction "2_2") (pintype "passive"))
    )
    (net (code "27") (name "Net-(IC4A-+IN)") (class "Default")
      (node (ref "IC4") (pin "3") (pinfunction "+IN_3") (pintype "input"))
      (node (ref "R14") (pin "2") (pinfunction "2_2") (pintype "passive"))
      (node (ref "R16") (pin "1") (pinfunction "1_1") (pintype "passive"))
    )
    (net (code "28") (name "Net-(IC4B-+IN)") (class "Default")
      (node (ref "IC4") (pin "5") (pinfunction "+IN_5") (pintype "input"))
      (node (ref "R13") (pin "2") (pinfunction "2_2") (pintype "passive"))
      (node (ref "R15") (pin "1") (pinfunction "1_1") (pintype "passive"))
    )
    (net (code "29") (name "Net-(IC5A-+IN)") (class "Default")
      (node (ref "C7") (pin "2") (pinfunction "2_2") (pintype "passive"))
      (node (ref "C8") (pin "2") (pinfunction "2_2") (pintype "passive"))
      (node (ref "IC5") (pin "3") (pinfunction "+IN_3") (pintype "input"))
      (node (ref "IC6") (pin "7") (pinfunction "OUT_7") (pintype "output"))
      (node (ref "R45") (pin "2") (pinfunction "2_2") (pintype "passive"))
      (node (ref "R47") (pin "1") (pinfunction "1_1") (pintype "passive"))
    )
    (net (code "30") (name "Net-(IC5A--IN)") (class "Default")
      (node (ref "IC5") (pin "2") (pinfunction "-IN_2") (pintype "input"))
      (node (ref "R44") (pin "2") (pinfunction "2_2") (pintype "passive"))
      (node (ref "R48") (pin "1") (pinfunction "1_1") (pintype "passive"))
    )
    (net (code "31") (name "Net-(IC5A-OUT)") (class "Default")
      (node (ref "IC5") (pin "1") (pinfunction "OUT_1") (pintype "output"))
      (node (ref "R48") (pin "2") (pinfunction "2_2") (pintype "passive"))
      (node (ref "R59") (pin "P$3") (pinfunction "A_P$3") (pintype "passive"))
    )
    (net (code "32") (name "Net-(IC5C-+IN)") (class "Default")
      (node (ref "IC5") (pin "10") (pinfunction "+IN_10") (pintype "input"))
      (node (ref "Q1") (pin "3") (pinfunction "C_3") (pintype "passive"))
      (node (ref "R20") (pin "1") (pinfunction "1_1") (pintype "passive"))
      (node (ref "R21") (pin "2") (pinfunction "2_2") (pintype "passive"))
    )
    (net (code "33") (name "Net-(IC5C--IN)") (class "Default")
      (node (ref "IC5") (pin "9") (pinfunction "-IN_9") (pintype "input"))
      (node (ref "R19") (pin "1") (pinfunction "1_1") (pintype "passive"))
      (node (ref "R22") (pin "2") (pinfunction "2_2") (pintype "passive"))
    )
    (net (code "34") (name "Net-(IC5D--IN)") (class "Default")
      (node (ref "IC5") (pin "13") (pinfunction "-IN_13") (pintype "input"))
      (node (ref "R23") (pin "1") (pinfunction "1_1") (pintype "passive"))
      (node (ref "R26") (pin "2") (pinfunction "2_2") (pintype "passive"))
      (node (ref "R29") (pin "2") (pinfunction "2_2") (pintype "passive"))
    )
    (net (code "35") (name "Net-(IC6A--IN)") (class "Default")
      (node (ref "IC6") (pin "2") (pinfunction "-IN_2") (pintype "input"))
      (node (ref "R30") (pin "2") (pinfunction "2_2") (pintype "passive"))
      (node (ref "R31") (pin "2") (pinfunction "2_2") (pintype "passive"))
      (node (ref "R32") (pin "1") (pinfunction "1_1") (pintype "passive"))
      (node (ref "R33") (pin "1") (pinfunction "1_1") (pintype "passive"))
    )
    (net (code "36") (name "Net-(IC6A-OUT)") (class "Default")
      (node (ref "IC6") (pin "1") (pinfunction "OUT_1") (pintype "output"))
      (node (ref "R33") (pin "2") (pinfunction "2_2") (pintype "passive"))
      (node (ref "R34") (pin "1") (pinfunction "1_1") (pintype "passive"))
    )
    (net (code "37") (name "Net-(IC6D--IN)") (class "Default")
      (node (ref "D5") (pin "A") (pinfunction "A_A") (pintype "passive"))
      (node (ref "IC6") (pin "13") (pinfunction "-IN_13") (pintype "input"))
      (node (ref "R41") (pin "2") (pinfunction "2_2") (pintype "passive"))
      (node (ref "R42") (pin "2") (pinfunction "2_2") (pintype "passive"))
      (node (ref "R43") (pin "2") (pinfunction "2_2") (pintype "passive"))
      (node (ref "R45") (pin "1") (pinfunction "1_1") (pintype "passive"))
      (node (ref "R46") (pin "1") (pinfunction "1_1") (pintype "passive"))
    )
    (net (code "38") (name "Net-(IC6D-OUT)") (class "Default")
      (node (ref "D5") (pin "C") (pinfunction "C_C") (pintype "passive"))
      (node (ref "D6") (pin "A") (pinfunction "A_A") (pintype "passive"))
      (node (ref "IC6") (pin "14") (pinfunction "OUT_14") (pintype "output"))
    )
    (net (code "39") (name "Net-(J1-3)") (class "Default")
      (node (ref "J1") (pin "P3") (pinfunction "3_P3") (pintype "passive"))
      (node (ref "R51") (pin "P$1") (pinfunction "E_P$1") (pintype "passive"))
    )
    (net (code "40") (name "Net-(J2-3)") (class "Default")
      (node (ref "J2") (pin "P3") (pinfunction "3_P3") (pintype "passive"))
      (node (ref "R52") (pin "P$1") (pinfunction "E_P$1") (pintype "passive"))
    )
    (net (code "41") (name "Net-(J3-3)") (class "Default")
      (node (ref "C5") (pin "1") (pinfunction "1_1") (pintype "passive"))
      (node (ref "J3") (pin "P3") (pinfunction "3_P3") (pintype "passive"))
    )
    (net (code "42") (name "Net-(J4-3)") (class "Default")
      (node (ref "J4") (pin "P3") (pinfunction "3_P3") (pintype "passive"))
      (node (ref "R53") (pin "P$1") (pinfunction "E_P$1") (pintype "passive"))
    )
    (net (code "43") (name "Net-(Q1-B)") (class "Default")
      (node (ref "Q1") (pin "1") (pinfunction "B_1") (pintype "passive"))
      (node (ref "R17") (pin "2") (pinfunction "2_2") (pintype "passive"))
      (node (ref "SW1") (pin "P$2") (pinfunction "P$2_P$2") (pintype "passive"))
    )
    (net (code "44") (name "Net-(R18-Pad2)") (class "Default")
      (node (ref "R18") (pin "2") (pinfunction "2_2") (pintype "passive"))
      (node (ref "SW1") (pin "P$1") (pinfunction "P$1_P$1") (pintype "passive"))
    )
    (net (code "45") (name "Net-(R24-Pad1)") (class "Default")
      (node (ref "R24") (pin "1") (pinfunction "1_1") (pintype "passive"))
      (node (ref "R26") (pin "1") (pinfunction "1_1") (pintype "passive"))
      (node (ref "R27") (pin "2") (pinfunction "2_2") (pintype "passive"))
    )
    (net (code "46") (name "Net-(R25-Pad1)") (class "Default")
      (node (ref "R25") (pin "1") (pinfunction "1_1") (pintype "passive"))
      (node (ref "R27") (pin "1") (pinfunction "1_1") (pintype "passive"))
      (node (ref "R28") (pin "2") (pinfunction "2_2") (pintype "passive"))
    )
    (net (code "47") (name "Net-(R31-Pad1)") (class "Default")
      (node (ref "R31") (pin "1") (pinfunction "1_1") (pintype "passive"))
      (node (ref "R35") (pin "2") (pinfunction "2_2") (pintype "passive"))
      (node (ref "R36") (pin "2") (pinfunction "2_2") (pintype "passive"))
      (node (ref "R38") (pin "2") (pinfunction "2_2") (pintype "passive"))
      (node (ref "R44") (pin "1") (pinfunction "1_1") (pintype "passive"))
    )
    (net (code "48") (name "Net-(R51-S)") (class "Default")
      (node (ref "R1") (pin "1") (pinfunction "1_1") (pintype "passive"))
      (node (ref "R51") (pin "P$2") (pinfunction "S_P$2") (pintype "passive"))
    )
    (net (code "49") (name "Net-(R52-S)") (class "Default")
      (node (ref "R2") (pin "1") (pinfunction "1_1") (pintype "passive"))
      (node (ref "R52") (pin "P$2") (pinfunction "S_P$2") (pintype "passive"))
    )
    (net (code "50") (name "Net-(R53-S)") (class "Default")
      (node (ref "R41") (pin "1") (pinfunction "1_1") (pintype "passive"))
      (node (ref "R53") (pin "P$2") (pinfunction "S_P$2") (pintype "passive"))
    )
    (net (code "51") (name "Net-(R54-S)") (class "Default")
      (node (ref "R3") (pin "1") (pinfunction "1_1") (pintype "passive"))
      (node (ref "R54") (pin "P$2") (pinfunction "S_P$2") (pintype "passive"))
    )
    (net (code "52") (name "Net-(R55-S)") (class "Default")
      (node (ref "R4") (pin "1") (pinfunction "1_1") (pintype "passive"))
      (node (ref "R55") (pin "P$2") (pinfunction "S_P$2") (pintype "passive"))
    )
    (net (code "53") (name "Net-(R56-S)") (class "Default")
      (node (ref "R5") (pin "1") (pinfunction "1_1") (pintype "passive"))
      (node (ref "R56") (pin "P$2") (pinfunction "S_P$2") (pintype "passive"))
    )
    (net (code "54") (name "Net-(R57-S)") (class "Default")
      (node (ref "R57") (pin "P$2") (pinfunction "S_P$2") (pintype "passive"))
      (node (ref "R6") (pin "1") (pinfunction "1_1") (pintype "passive"))
    )
    (net (code "55") (name "Net-(R58-S)") (class "Default")
      (node (ref "R43") (pin "1") (pinfunction "1_1") (pintype "passive"))
      (node (ref "R58") (pin "P$2") (pinfunction "S_P$2") (pintype "passive"))
    )
    (net (code "56") (name "Net-(R59-S)") (class "Default")
      (node (ref "R39") (pin "1") (pinfunction "1_1") (pintype "passive"))
      (node (ref "R40") (pin "2") (pinfunction "2_2") (pintype "passive"))
      (node (ref "R59") (pin "P$2") (pinfunction "S_P$2") (pintype "passive"))
    )
    (net (code "57") (name "Net-(R60-S)") (class "Default")
      (node (ref "R18") (pin "1") (pinfunction "1_1") (pintype "passive"))
      (node (ref "R60") (pin "P$2") (pinfunction "S_P$2") (pintype "passive"))
    )
    (net (code "58") (name "Net-(R61-S)") (class "Default")
      (node (ref "R42") (pin "1") (pinfunction "1_1") (pintype "passive"))
      (node (ref "R61") (pin "P$2") (pinfunction "S_P$2") (pintype "passive"))
    )
    (net (code "59") (name "OUT") (class "Default")
      (node (ref "C10") (pin "2") (pinfunction "2_2") (pintype "passive"))
      (node (ref "IC5") (pin "7") (pinfunction "OUT_7") (pintype "output"))
      (node (ref "J9") (pin "P3") (pinfunction "3_P3") (pintype "passive"))
      (node (ref "R32") (pin "2") (pinfunction "2_2") (pintype "passive"))
      (node (ref "R50") (pin "2") (pinfunction "2_2") (pintype "passive"))
    )
    (net (code "60") (name "P1") (class "Default")
      (node (ref "IC4") (pin "7") (pinfunction "OUT_7") (pintype "output"))
      (node (ref "J8") (pin "P3") (pinfunction "3_P3") (pintype "passive"))
      (node (ref "R11") (pin "2") (pinfunction "2_2") (pintype "passive"))
      (node (ref "R15") (pin "2") (pinfunction "2_2") (pintype "passive"))
      (node (ref "R17") (pin "1") (pinfunction "1_1") (pintype "passive"))
    )
    (net (code "61") (name "P2") (class "Default")
      (node (ref "IC1") (pin "10") (pinfunction "CLK_10") (pintype "input"))
      (node (ref "IC4") (pin "1") (pinfunction "OUT_1") (pintype "output"))
      (node (ref "J5") (pin "P3") (pinfunction "3_P3") (pintype "passive"))
      (node (ref "R12") (pin "2") (pinfunction "2_2") (pintype "passive"))
      (node (ref "R16") (pin "2") (pinfunction "2_2") (pintype "passive"))
    )
    (net (code "62") (name "PWM") (class "Default")
      (node (ref "IC6") (pin "8") (pinfunction "OUT_8") (pintype "output"))
      (node (ref "J10") (pin "P3") (pinfunction "3_P3") (pintype "passive"))
      (node (ref "R36") (pin "1") (pinfunction "1_1") (pintype "passive"))
    )
    (net (code "63") (name "RUN_CV") (class "Default")
      (node (ref "IC5") (pin "14") (pinfunction "OUT_14") (pintype "output"))
      (node (ref "J11") (pin "P3") (pinfunction "3_P3") (pintype "passive"))
      (node (ref "R29") (pin "1") (pinfunction "1_1") (pintype "passive"))
      (node (ref "R35") (pin "1") (pinfunction "1_1") (pintype "passive"))
      (node (ref "R55") (pin "P$1") (pinfunction "E_P$1") (pintype "passive"))
      (node (ref "R57") (pin "P$1") (pinfunction "E_P$1") (pintype "passive"))
      (node (ref "R61") (pin "P$1") (pinfunction "E_P$1") (pintype "passive"))
    )
    (net (code "64") (name "T1") (class "Default")
      (node (ref "C3") (pin "2") (pinfunction "2_2") (pintype "passive"))
      (node (ref "IC2") (pin "14") (pinfunction "OUT_14") (pintype "output"))
      (node (ref "IC6") (pin "9") (pinfunction "-IN_9") (pintype "input"))
      (node (ref "J6") (pin "P3") (pinfunction "3_P3") (pintype "passive"))
      (node (ref "R13") (pin "1") (pinfunction "1_1") (pintype "passive"))
    )
    (net (code "65") (name "T2") (class "Default")
      (node (ref "C4") (pin "2") (pinfunction "2_2") (pintype "passive"))
      (node (ref "IC2") (pin "7") (pinfunction "OUT_7") (pintype "output"))
      (node (ref "IC6") (pin "10") (pinfunction "+IN_10") (pintype "input"))
      (node (ref "J7") (pin "P3") (pinfunction "3_P3") (pintype "passive"))
      (node (ref "R14") (pin "1") (pinfunction "1_1") (pintype "passive"))
    )
    (net (code "66") (name "V+") (class "Default")
      (node (ref "C13") (pin "1") (pinfunction "1_1") (pintype "passive"))
      (node (ref "C15") (pin "+") (pinfunction "+_+") (pintype "passive"))
      (node (ref "C17") (pin "1") (pinfunction "1_1") (pintype "passive"))
      (node (ref "C19") (pin "1") (pinfunction "1_1") (pintype "passive"))
      (node (ref "C21") (pin "1") (pinfunction "1_1") (pintype "passive"))
      (node (ref "C23") (pin "1") (pinfunction "1_1") (pintype "passive"))
      (node (ref "C25") (pin "1") (pinfunction "1_1") (pintype "passive"))
      (node (ref "C27") (pin "1") (pinfunction "1_1") (pintype "passive"))
      (node (ref "D7") (pin "2") (pinfunction "-_2") (pintype "passive"))
      (node (ref "D8") (pin "1") (pinfunction "+_1") (pintype "passive"))
      (node (ref "IC1") (pin "16") (pinfunction "VDD_16") (pintype "power_in"))
      (node (ref "IC2") (pin "4") (pinfunction "V+_4") (pintype "power_in"))
      (node (ref "IC3") (pin "16") (pinfunction "V+_16") (pintype "power_in"))
      (node (ref "IC4") (pin "8") (pinfunction "V+_8") (pintype "power_in"))
      (node (ref "IC5") (pin "4") (pinfunction "V+_4") (pintype "power_in"))
      (node (ref "IC6") (pin "4") (pinfunction "V+_4") (pintype "power_in"))
      (node (ref "IC7") (pin "OUT") (pinfunction "OUT_OUT") (pintype "passive"))
      (node (ref "R60") (pin "P$1") (pinfunction "E_P$1") (pintype "passive"))
    )
    (net (code "67") (name "V-") (class "Default")
      (node (ref "C14") (pin "2") (pinfunction "2_2") (pintype "passive"))
      (node (ref "C16") (pin "-") (pinfunction "-_-") (pintype "passive"))
      (node (ref "C18") (pin "2") (pinfunction "2_2") (pintype "passive"))
      (node (ref "C20") (pin "2") (pinfunction "2_2") (pintype "passive"))
      (node (ref "C22") (pin "2") (pinfunction "2_2") (pintype "passive"))
      (node (ref "C24") (pin "2") (pinfunction "2_2") (pintype "passive"))
      (node (ref "C26") (pin "2") (pinfunction "2_2") (pintype "passive"))
      (node (ref "C28") (pin "2") (pinfunction "2_2") (pintype "passive"))
      (node (ref "D10") (pin "1") (pinfunction "+_1") (pintype "passive"))
      (node (ref "D11") (pin "A") (pinfunction "A_A") (pintype "passive"))
      (node (ref "D9") (pin "2") (pinfunction "-_2") (pintype "passive"))
      (node (ref "IC1") (pin "8") (pinfunction "VSS_8") (pintype "power_in"))
      (node (ref "IC1") (pin "9") (pinfunction "P/~{S}_9") (pintype "input"))
      (node (ref "IC2") (pin "11") (pinfunction "V-_11") (pintype "power_in"))
      (node (ref "IC3") (pin "9") (pinfunction "V-_9") (pintype "power_in"))
      (node (ref "IC4") (pin "4") (pinfunction "V-_4") (pintype "power_in"))
      (node (ref "IC5") (pin "11") (pinfunction "V-_11") (pintype "power_in"))
      (node (ref "IC6") (pin "11") (pinfunction "V-_11") (pintype "power_in"))
      (node (ref "IC8") (pin "OUT") (pinfunction "OUT_OUT") (pintype "passive"))
      (node (ref "R54") (pin "P$3") (pinfunction "A_P$3") (pintype "passive"))
      (node (ref "R56") (pin "P$3") (pinfunction "A_P$3") (pintype "passive"))
      (node (ref "R58") (pin "P$3") (pinfunction "A_P$3") (pintype "passive"))
      (node (ref "R60") (pin "P$3") (pinfunction "A_P$3") (pintype "passive"))
    )
    (net (code "68") (name "VCC") (class "Default")
      (node (ref "C100") (pin "+") (pinfunction "+_+") (pintype "passive"))
      (node (ref "C11") (pin "1") (pinfunction "1_1") (pintype "passive"))
      (node (ref "D100") (pin "C") (pinfunction "C_C") (pintype "passive"))
      (node (ref "D8") (pin "2") (pinfunction "-_2") (pintype "passive"))
      (node (ref "IC7") (pin "IN") (pinfunction "IN_IN") (pintype "input"))
    )
    (net (code "69") (name "VEE") (class "Default")
      (node (ref "C12") (pin "2") (pinfunction "2_2") (pintype "passive"))
      (node (ref "C200") (pin "-") (pinfunction "-_-") (pintype "passive"))
      (node (ref "D200") (pin "A") (pinfunction "A_A") (pintype "passive"))
      (node (ref "D9") (pin "1") (pinfunction "+_1") (pintype "passive"))
      (node (ref "IC8") (pin "IN") (pinfunction "IN_IN") (pintype "input"))
    )
    (net (code "70") (name "XOR") (class "Default")
      (node (ref "IC1") (pin "11") (pinfunction "SI_11") (pintype "input"))
      (node (ref "IC5") (pin "8") (pinfunction "OUT_8") (pintype "output"))
      (node (ref "J12") (pin "P3") (pinfunction "3_P3") (pintype "passive"))
      (node (ref "R22") (pin "1") (pinfunction "1_1") (pintype "passive"))
    )
    (net (code "71") (name "unconnected-(IC1A-P1-Pad7)") (class "Default")
      (node (ref "IC1") (pin "7") (pinfunction "P1_7") (pintype "input"))
    )
    (net (code "72") (name "unconnected-(IC1A-P2-Pad6)") (class "Default")
      (node (ref "IC1") (pin "6") (pinfunction "P2_6") (pintype "input"))
    )
    (net (code "73") (name "unconnected-(IC1A-P3-Pad5)") (class "Default")
      (node (ref "IC1") (pin "5") (pinfunction "P3_5") (pintype "input"))
    )
    (net (code "74") (name "unconnected-(IC1A-P4-Pad4)") (class "Default")
      (node (ref "IC1") (pin "4") (pinfunction "P4_4") (pintype "input"))
    )
    (net (code "75") (name "unconnected-(IC1A-P5-Pad13)") (class "Default")
      (node (ref "IC1") (pin "13") (pinfunction "P5_13") (pintype "input"))
    )
    (net (code "76") (name "unconnected-(IC1A-P6-Pad14)") (class "Default")
      (node (ref "IC1") (pin "14") (pinfunction "P6_14") (pintype "input"))
    )
    (net (code "77") (name "unconnected-(IC1A-P7-Pad15)") (class "Default")
      (node (ref "IC1") (pin "15") (pinfunction "P7_15") (pintype "input"))
    )
    (net (code "78") (name "unconnected-(IC1A-P8-Pad1)") (class "Default")
      (node (ref "IC1") (pin "1") (pinfunction "P8_1") (pintype "input"))
    )
    (net (code "79") (name "unconnected-(IC3E-MODE-Pad1)") (class "Default")
      (node (ref "IC3") (pin "1") (pinfunction "MODE_1") (pintype "input"))
    )
    (net (code "80") (name "unconnected-(J1-2-PadP2)") (class "Default")
      (node (ref "J1") (pin "P2") (pinfunction "2_P2") (pintype "passive"))
    )
    (net (code "81") (name "unconnected-(J2-2-PadP2)") (class "Default")
      (node (ref "J2") (pin "P2") (pinfunction "2_P2") (pintype "passive"))
    )
    (net (code "82") (name "unconnected-(J3-2-PadP2)") (class "Default")
      (node (ref "J3") (pin "P2") (pinfunction "2_P2") (pintype "passive"))
    )
    (net (code "83") (name "unconnected-(J4-2-PadP2)") (class "Default")
      (node (ref "J4") (pin "P2") (pinfunction "2_P2") (pintype "passive"))
    )
    (net (code "84") (name "unconnected-(J5-2-PadP2)") (class "Default")
      (node (ref "J5") (pin "P2") (pinfunction "2_P2") (pintype "passive"))
    )
    (net (code "85") (name "unconnected-(J6-2-PadP2)") (class "Default")
      (node (ref "J6") (pin "P2") (pinfunction "2_P2") (pintype "passive"))
    )
    (net (code "86") (name "unconnected-(J7-2-PadP2)") (class "Default")
      (node (ref "J7") (pin "P2") (pinfunction "2_P2") (pintype "passive"))
    )
    (net (code "87") (name "unconnected-(J8-2-PadP2)") (class "Default")
      (node (ref "J8") (pin "P2") (pinfunction "2_P2") (pintype "passive"))
    )
    (net (code "88") (name "unconnected-(J9-2-PadP2)") (class "Default")
      (node (ref "J9") (pin "P2") (pinfunction "2_P2") (pintype "passive"))
    )
    (net (code "89") (name "unconnected-(J10-2-PadP2)") (class "Default")
      (node (ref "J10") (pin "P2") (pinfunction "2_P2") (pintype "passive"))
    )
    (net (code "90") (name "unconnected-(J11-2-PadP2)") (class "Default")
      (node (ref "J11") (pin "P2") (pinfunction "2_P2") (pintype "passive"))
    )
    (net (code "91") (name "unconnected-(J12-2-PadP2)") (class "Default")
      (node (ref "J12") (pin "P2") (pinfunction "2_P2") (pintype "passive"))
    )
    (net (code "92") (name "unconnected-(SW1-PadP$3)") (class "Default")
      (node (ref "SW1") (pin "P$3") (pinfunction "P$3_P$3") (pintype "passive"))
    )
  )
)
